# Placa_do_uControlador.net
KiCad netlist of a schematic drawn in Altium Designer
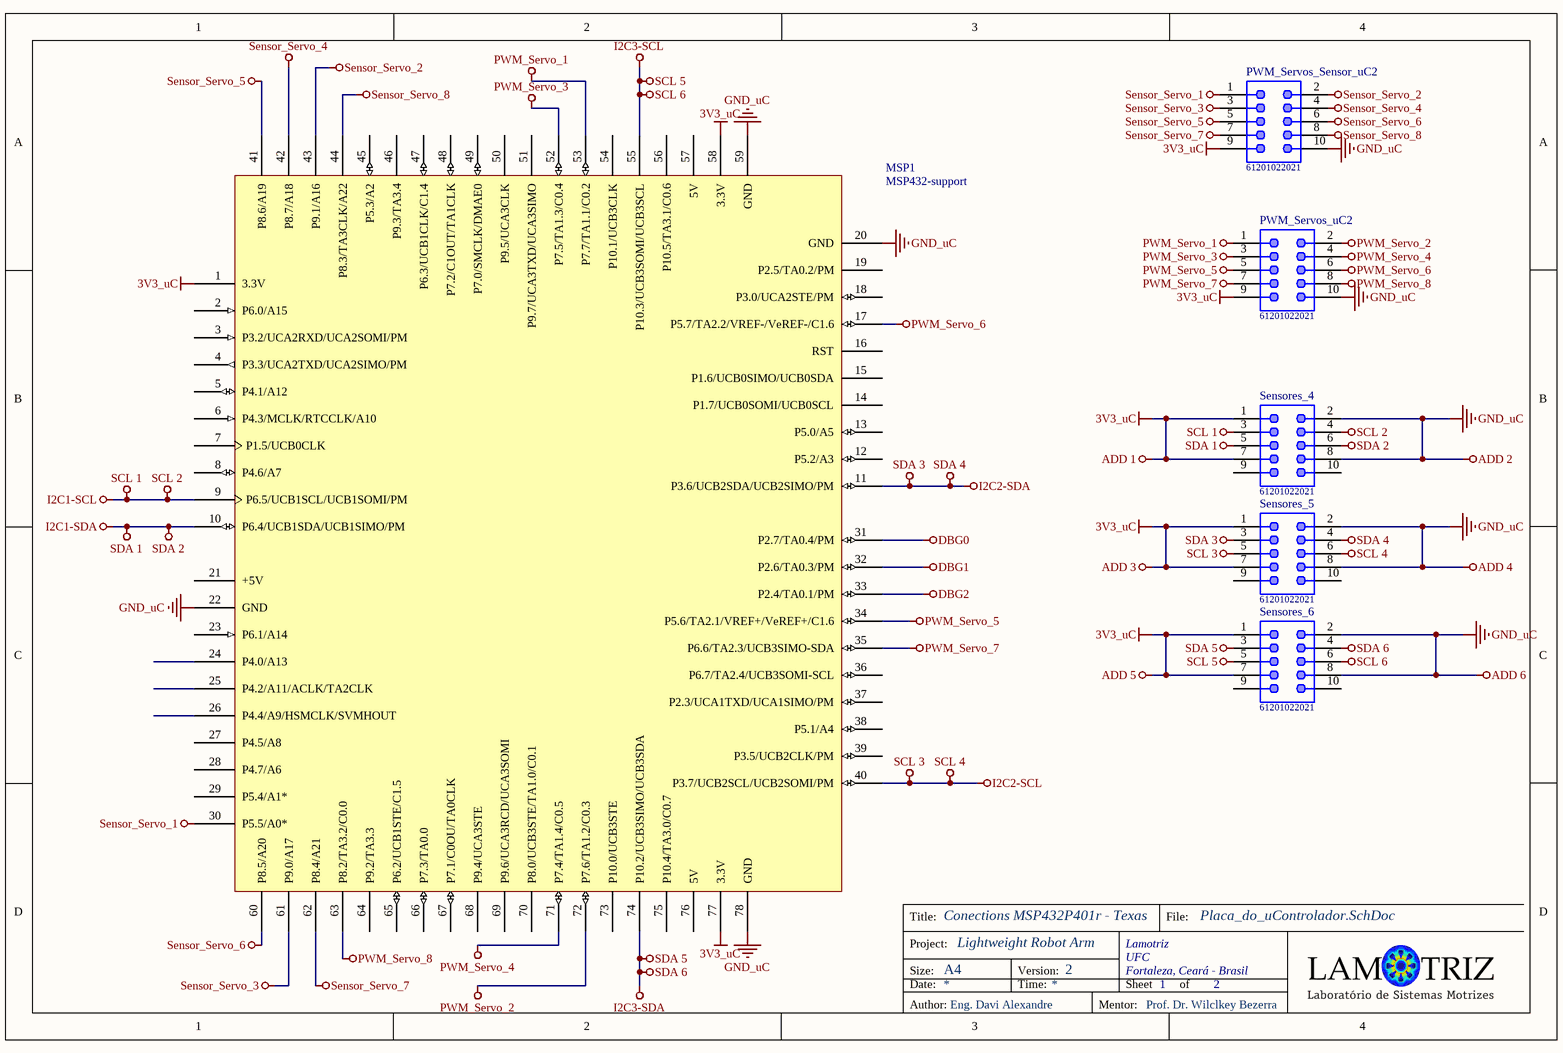
[diagram p0: Placa_do_uControlador.SchDoc]

(export (version "E")
  (design (tool "Eeschema 10.0.6"))
  (components
    (comp (ref "MSP1")
      (value "MSP432-support")
      (footprint "Msp432_Suport")
      (libsource (lib "Msp432_Suport") (part "U*"))
    )
    (comp (ref "PWM_Servos_Sensor_uC2")
      (value "61201022021")
      (footprint "61201022021")
      (description "Male Box Header WR-BHD with lever, THT, Vertical, pitch 2.54 mm, 10 pins")
      (fields (field (name "PUBLISHER") "Wurth Elektronik"))
      (libsource (lib "62504022021_Altium_WR-BHD_rev19a") (part "61201022021"))
    )
    (comp (ref "PWM_Servos_uC2")
      (value "61201022021")
      (footprint "61201022021")
      (description "Male Box Header WR-BHD with lever, THT, Vertical, pitch 2.54 mm, 10 pins")
      (fields (field (name "PUBLISHER") "Wurth Elektronik"))
      (libsource (lib "62504022021_Altium_WR-BHD_rev19a") (part "61201022021"))
    )
    (comp (ref "Sensores_4")
      (value "61201022021")
      (footprint "61201022021")
      (description "Male Box Header WR-BHD with lever, THT, Vertical, pitch 2.54 mm, 10 pins")
      (fields (field (name "PUBLISHER") "Wurth Elektronik"))
      (libsource (lib "62504022021_Altium_WR-BHD_rev19a") (part "61201022021"))
    )
    (comp (ref "Sensores_5")
      (value "61201022021")
      (footprint "61201022021")
      (description "Male Box Header WR-BHD with lever, THT, Vertical, pitch 2.54 mm, 10 pins")
      (fields (field (name "PUBLISHER") "Wurth Elektronik"))
      (libsource (lib "62504022021_Altium_WR-BHD_rev19a") (part "61201022021"))
    )
    (comp (ref "Sensores_6")
      (value "61201022021")
      (footprint "61201022021")
      (description "Male Box Header WR-BHD with lever, THT, Vertical, pitch 2.54 mm, 10 pins")
      (fields (field (name "PUBLISHER") "Wurth Elektronik"))
      (libsource (lib "62504022021_Altium_WR-BHD_rev19a") (part "61201022021"))
    )
  )
  (nets
    (net (code "1") (name "3V3_uC") (class "Default")
      (node (ref "MSP1") (pin "1") (pinfunction "3.3V_1") (pintype "power_in"))
      (node (ref "MSP1") (pin "58") (pinfunction "3.3V_58") (pintype "power_in"))
      (node (ref "MSP1") (pin "77") (pinfunction "3.3V_77") (pintype "power_in"))
      (node (ref "PWM_Servos_Sensor_uC2") (pin "9") (pinfunction "9_9") (pintype "passive"))
      (node (ref "PWM_Servos_uC2") (pin "9") (pinfunction "9_9") (pintype "passive"))
      (node (ref "Sensores_4") (pin "1") (pinfunction "1_1") (pintype "passive"))
      (node (ref "Sensores_4") (pin "7") (pinfunction "7_7") (pintype "passive"))
      (node (ref "Sensores_5") (pin "1") (pinfunction "1_1") (pintype "passive"))
      (node (ref "Sensores_5") (pin "7") (pinfunction "7_7") (pintype "passive"))
      (node (ref "Sensores_6") (pin "1") (pinfunction "1_1") (pintype "passive"))
      (node (ref "Sensores_6") (pin "7") (pinfunction "7_7") (pintype "passive"))
    )
    (net (code "2") (name "ADD 2") (class "Default")
      (node (ref "MSP1") (pin "20") (pinfunction "GND_20") (pintype "power_in"))
      (node (ref "MSP1") (pin "22") (pinfunction "GND_22") (pintype "passive"))
      (node (ref "MSP1") (pin "59") (pinfunction "GND_59") (pintype "power_in"))
      (node (ref "MSP1") (pin "78") (pinfunction "GND_78") (pintype "power_in"))
      (node (ref "PWM_Servos_Sensor_uC2") (pin "10") (pinfunction "10_10") (pintype "passive"))
      (node (ref "PWM_Servos_uC2") (pin "10") (pinfunction "10_10") (pintype "passive"))
      (node (ref "Sensores_4") (pin "2") (pinfunction "2_2") (pintype "passive"))
      (node (ref "Sensores_4") (pin "8") (pinfunction "8_8") (pintype "passive"))
      (node (ref "Sensores_5") (pin "2") (pinfunction "2_2") (pintype "passive"))
      (node (ref "Sensores_5") (pin "8") (pinfunction "8_8") (pintype "passive"))
      (node (ref "Sensores_6") (pin "2") (pinfunction "2_2") (pintype "passive"))
      (node (ref "Sensores_6") (pin "8") (pinfunction "8_8") (pintype "passive"))
    )
    (net (code "3") (name "DBG0") (class "Default")
      (node (ref "MSP1") (pin "31") (pinfunction "P2.7/TA0.4/PM_31") (pintype "bidirectional"))
    )
    (net (code "4") (name "DBG1") (class "Default")
      (node (ref "MSP1") (pin "32") (pinfunction "P2.6/TA0.3/PM_32") (pintype "bidirectional"))
    )
    (net (code "5") (name "DBG2") (class "Default")
      (node (ref "MSP1") (pin "33") (pinfunction "P2.4/TA0.1/PM_33") (pintype "bidirectional"))
    )
    (net (code "6") (name "I2C1-SCL") (class "Default")
      (node (ref "MSP1") (pin "9") (pinfunction "P6.5/UCB1SCL/UCB1SOMI/PM_9") (pintype "passive"))
      (node (ref "Sensores_4") (pin "3") (pinfunction "3_3") (pintype "passive"))
      (node (ref "Sensores_4") (pin "4") (pinfunction "4_4") (pintype "passive"))
    )
    (net (code "7") (name "I2C1-SDA") (class "Default")
      (node (ref "MSP1") (pin "10") (pinfunction "P6.4/UCB1SDA/UCB1SIMO/PM_10") (pintype "bidirectional"))
      (node (ref "Sensores_4") (pin "5") (pinfunction "5_5") (pintype "passive"))
      (node (ref "Sensores_4") (pin "6") (pinfunction "6_6") (pintype "passive"))
    )
    (net (code "8") (name "I2C2-SCL") (class "Default")
      (node (ref "MSP1") (pin "40") (pinfunction "P3.7/UCB2SCL/UCB2SOMI/PM_40") (pintype "bidirectional"))
      (node (ref "Sensores_5") (pin "5") (pinfunction "5_5") (pintype "passive"))
      (node (ref "Sensores_5") (pin "6") (pinfunction "6_6") (pintype "passive"))
    )
    (net (code "9") (name "I2C2-SDA") (class "Default")
      (node (ref "MSP1") (pin "11") (pinfunction "P3.6/UCB2SDA/UCB2SIMO/PM_11") (pintype "bidirectional"))
      (node (ref "Sensores_5") (pin "3") (pinfunction "3_3") (pintype "passive"))
      (node (ref "Sensores_5") (pin "4") (pinfunction "4_4") (pintype "passive"))
    )
    (net (code "10") (name "I2C3-SCL") (class "Default")
      (node (ref "MSP1") (pin "55") (pinfunction "P10.3/UCB3SOMI/UCB3SCL_55") (pintype "passive"))
      (node (ref "Sensores_6") (pin "5") (pinfunction "5_5") (pintype "passive"))
      (node (ref "Sensores_6") (pin "6") (pinfunction "6_6") (pintype "passive"))
    )
    (net (code "11") (name "I2C3-SDA") (class "Default")
      (node (ref "MSP1") (pin "74") (pinfunction "P10.2/UCB3SIMO/UCB3SDA_74") (pintype "passive"))
      (node (ref "Sensores_6") (pin "3") (pinfunction "3_3") (pintype "passive"))
      (node (ref "Sensores_6") (pin "4") (pinfunction "4_4") (pintype "passive"))
    )
    (net (code "12") (name "PWM_Servo_1") (class "Default")
      (node (ref "MSP1") (pin "53") (pinfunction "P7.7/TA1.1/C0.2_53") (pintype "bidirectional"))
      (node (ref "PWM_Servos_uC2") (pin "1") (pinfunction "1_1") (pintype "passive"))
    )
    (net (code "13") (name "PWM_Servo_2") (class "Default")
      (node (ref "MSP1") (pin "72") (pinfunction "P7.6/TA1.2/C0.3_72") (pintype "bidirectional"))
      (node (ref "PWM_Servos_uC2") (pin "2") (pinfunction "2_2") (pintype "passive"))
    )
    (net (code "14") (name "PWM_Servo_3") (class "Default")
      (node (ref "MSP1") (pin "52") (pinfunction "P7.5/TA1.3/C0.4_52") (pintype "bidirectional"))
      (node (ref "PWM_Servos_uC2") (pin "3") (pinfunction "3_3") (pintype "passive"))
    )
    (net (code "15") (name "PWM_Servo_4") (class "Default")
      (node (ref "MSP1") (pin "71") (pinfunction "P7.4/TA1.4/C0.5_71") (pintype "bidirectional"))
      (node (ref "PWM_Servos_uC2") (pin "4") (pinfunction "4_4") (pintype "passive"))
    )
    (net (code "16") (name "PWM_Servo_5") (class "Default")
      (node (ref "MSP1") (pin "34") (pinfunction "P5.6/TA2.1/VREF+/VeREF+/C1.6_34") (pintype "bidirectional"))
      (node (ref "PWM_Servos_uC2") (pin "5") (pinfunction "5_5") (pintype "passive"))
    )
    (net (code "17") (name "PWM_Servo_6") (class "Default")
      (node (ref "MSP1") (pin "17") (pinfunction "P5.7/TA2.2/VREF-/VeREF-/C1.6_17") (pintype "bidirectional"))
      (node (ref "PWM_Servos_uC2") (pin "6") (pinfunction "6_6") (pintype "passive"))
    )
    (net (code "18") (name "PWM_Servo_7") (class "Default")
      (node (ref "MSP1") (pin "35") (pinfunction "P6.6/TA2.3/UCB3SIMO-SDA_35") (pintype "bidirectional"))
      (node (ref "PWM_Servos_uC2") (pin "7") (pinfunction "7_7") (pintype "passive"))
    )
    (net (code "19") (name "PWM_Servo_8") (class "Default")
      (node (ref "MSP1") (pin "63") (pinfunction "P8.2/TA3.2/C0.0_63") (pintype "passive"))
      (node (ref "PWM_Servos_uC2") (pin "8") (pinfunction "8_8") (pintype "passive"))
    )
    (net (code "20") (name "Sensor_Servo_1") (class "Default")
      (node (ref "MSP1") (pin "30") (pinfunction "P5.5/A0*_30") (pintype "passive"))
      (node (ref "PWM_Servos_Sensor_uC2") (pin "1") (pinfunction "1_1") (pintype "passive"))
    )
    (net (code "21") (name "Sensor_Servo_2") (class "Default")
      (node (ref "MSP1") (pin "43") (pinfunction "P9.1/A16_43") (pintype "passive"))
      (node (ref "PWM_Servos_Sensor_uC2") (pin "2") (pinfunction "2_2") (pintype "passive"))
    )
    (net (code "22") (name "Sensor_Servo_3") (class "Default")
      (node (ref "MSP1") (pin "61") (pinfunction "P9.0/A17_61") (pintype "passive"))
      (node (ref "PWM_Servos_Sensor_uC2") (pin "3") (pinfunction "3_3") (pintype "passive"))
    )
    (net (code "23") (name "Sensor_Servo_4") (class "Default")
      (node (ref "MSP1") (pin "42") (pinfunction "P8.7/A18_42") (pintype "passive"))
      (node (ref "PWM_Servos_Sensor_uC2") (pin "4") (pinfunction "4_4") (pintype "passive"))
    )
    (net (code "24") (name "Sensor_Servo_5") (class "Default")
      (node (ref "MSP1") (pin "41") (pinfunction "P8.6/A19_41") (pintype "passive"))
      (node (ref "PWM_Servos_Sensor_uC2") (pin "5") (pinfunction "5_5") (pintype "passive"))
    )
    (net (code "25") (name "Sensor_Servo_6") (class "Default")
      (node (ref "MSP1") (pin "60") (pinfunction "P8.5/A20_60") (pintype "passive"))
      (node (ref "PWM_Servos_Sensor_uC2") (pin "6") (pinfunction "6_6") (pintype "passive"))
    )
    (net (code "26") (name "Sensor_Servo_7") (class "Default")
      (node (ref "MSP1") (pin "62") (pinfunction "P8.4/A21_62") (pintype "passive"))
      (node (ref "PWM_Servos_Sensor_uC2") (pin "7") (pinfunction "7_7") (pintype "passive"))
    )
    (net (code "27") (name "Sensor_Servo_8") (class "Default")
      (node (ref "MSP1") (pin "44") (pinfunction "P8.3/TA3CLK/A22_44") (pintype "passive"))
      (node (ref "PWM_Servos_Sensor_uC2") (pin "8") (pinfunction "8_8") (pintype "passive"))
    )
    (net (code "28") (name "unconnected-(MSP1-+5V-Pad21)") (class "Default")
      (node (ref "MSP1") (pin "21") (pinfunction "+5V_21") (pintype "power_in"))
    )
    (net (code "29") (name "unconnected-(MSP1-5V-Pad57)") (class "Default")
      (node (ref "MSP1") (pin "57") (pinfunction "5V_57") (pintype "power_in"))
    )
    (net (code "30") (name "unconnected-(MSP1-5V-Pad76)") (class "Default")
      (node (ref "MSP1") (pin "76") (pinfunction "5V_76") (pintype "power_in"))
    )
    (net (code "31") (name "unconnected-(MSP1-P1.5{slash}UCB0CLK-Pad7)") (class "Default")
      (node (ref "MSP1") (pin "7") (pinfunction "P1.5/UCB0CLK_7") (pintype "passive"))
    )
    (net (code "32") (name "unconnected-(MSP1-P1.6{slash}UCB0SIMO{slash}UCB0SDA-Pad15)") (class "Default")
      (node (ref "MSP1") (pin "15") (pinfunction "P1.6/UCB0SIMO/UCB0SDA_15") (pintype "passive"))
    )
    (net (code "33") (name "unconnected-(MSP1-P1.7{slash}UCB0SOMI{slash}UCB0SCL-Pad14)") (class "Default")
      (node (ref "MSP1") (pin "14") (pinfunction "P1.7/UCB0SOMI/UCB0SCL_14") (pintype "passive"))
    )
    (net (code "34") (name "unconnected-(MSP1-P2.3{slash}UCA1TXD{slash}UCA1SIMO{slash}PM-Pad37)") (class "Default")
      (node (ref "MSP1") (pin "37") (pinfunction "P2.3/UCA1TXD/UCA1SIMO/PM_37") (pintype "bidirectional"))
    )
    (net (code "35") (name "unconnected-(MSP1-P2.5{slash}TA0.2{slash}PM-Pad19)") (class "Default")
      (node (ref "MSP1") (pin "19") (pinfunction "P2.5/TA0.2/PM_19") (pintype "passive"))
    )
    (net (code "36") (name "unconnected-(MSP1-P3.0{slash}UCA2STE{slash}PM-Pad18)") (class "Default")
      (node (ref "MSP1") (pin "18") (pinfunction "P3.0/UCA2STE/PM_18") (pintype "bidirectional"))
    )
    (net (code "37") (name "unconnected-(MSP1-P3.2{slash}UCA2RXD{slash}UCA2SOMI{slash}PM-Pad3)") (class "Default")
      (node (ref "MSP1") (pin "3") (pinfunction "P3.2/UCA2RXD/UCA2SOMI/PM_3") (pintype "input"))
    )
    (net (code "38") (name "unconnected-(MSP1-P3.3{slash}UCA2TXD{slash}UCA2SIMO{slash}PM-Pad4)") (class "Default")
      (node (ref "MSP1") (pin "4") (pinfunction "P3.3/UCA2TXD/UCA2SIMO/PM_4") (pintype "output"))
    )
    (net (code "39") (name "unconnected-(MSP1-P3.5{slash}UCB2CLK{slash}PM-Pad39)") (class "Default")
      (node (ref "MSP1") (pin "39") (pinfunction "P3.5/UCB2CLK/PM_39") (pintype "bidirectional"))
    )
    (net (code "40") (name "unconnected-(MSP1-P4.0{slash}A13-Pad24)") (class "Default")
      (node (ref "MSP1") (pin "24") (pinfunction "P4.0/A13_24") (pintype "passive"))
    )
    (net (code "41") (name "unconnected-(MSP1-P4.1{slash}A12-Pad5)") (class "Default")
      (node (ref "MSP1") (pin "5") (pinfunction "P4.1/A12_5") (pintype "bidirectional"))
    )
    (net (code "42") (name "unconnected-(MSP1-P4.2{slash}A11{slash}ACLK{slash}TA2CLK-Pad25)") (class "Default")
      (node (ref "MSP1") (pin "25") (pinfunction "P4.2/A11/ACLK/TA2CLK_25") (pintype "passive"))
    )
    (net (code "43") (name "unconnected-(MSP1-P4.3{slash}MCLK{slash}RTCCLK{slash}A10-Pad6)") (class "Default")
      (node (ref "MSP1") (pin "6") (pinfunction "P4.3/MCLK/RTCCLK/A10_6") (pintype "input"))
    )
    (net (code "44") (name "unconnected-(MSP1-P4.4{slash}A9{slash}HSMCLK{slash}SVMHOUT-Pad26)") (class "Default")
      (node (ref "MSP1") (pin "26") (pinfunction "P4.4/A9/HSMCLK/SVMHOUT_26") (pintype "passive"))
    )
    (net (code "45") (name "unconnected-(MSP1-P4.5{slash}A8-Pad27)") (class "Default")
      (node (ref "MSP1") (pin "27") (pinfunction "P4.5/A8_27") (pintype "passive"))
    )
    (net (code "46") (name "unconnected-(MSP1-P4.6{slash}A7-Pad8)") (class "Default")
      (node (ref "MSP1") (pin "8") (pinfunction "P4.6/A7_8") (pintype "bidirectional"))
    )
    (net (code "47") (name "unconnected-(MSP1-P4.7{slash}A6-Pad28)") (class "Default")
      (node (ref "MSP1") (pin "28") (pinfunction "P4.7/A6_28") (pintype "passive"))
    )
    (net (code "48") (name "unconnected-(MSP1-P5.0{slash}A5-Pad13)") (class "Default")
      (node (ref "MSP1") (pin "13") (pinfunction "P5.0/A5_13") (pintype "bidirectional"))
    )
    (net (code "49") (name "unconnected-(MSP1-P5.1{slash}A4-Pad38)") (class "Default")
      (node (ref "MSP1") (pin "38") (pinfunction "P5.1/A4_38") (pintype "bidirectional"))
    )
    (net (code "50") (name "unconnected-(MSP1-P5.2{slash}A3-Pad12)") (class "Default")
      (node (ref "MSP1") (pin "12") (pinfunction "P5.2/A3_12") (pintype "bidirectional"))
    )
    (net (code "51") (name "unconnected-(MSP1-P5.3{slash}A2-Pad45)") (class "Default")
      (node (ref "MSP1") (pin "45") (pinfunction "P5.3/A2_45") (pintype "bidirectional"))
    )
    (net (code "52") (name "unconnected-(MSP1-P5.4{slash}A1*-Pad29)") (class "Default")
      (node (ref "MSP1") (pin "29") (pinfunction "P5.4/A1*_29") (pintype "passive"))
    )
    (net (code "53") (name "unconnected-(MSP1-P6.0{slash}A15-Pad2)") (class "Default")
      (node (ref "MSP1") (pin "2") (pinfunction "P6.0/A15_2") (pintype "input"))
    )
    (net (code "54") (name "unconnected-(MSP1-P6.1{slash}A14-Pad23)") (class "Default")
      (node (ref "MSP1") (pin "23") (pinfunction "P6.1/A14_23") (pintype "input"))
    )
    (net (code "55") (name "unconnected-(MSP1-P6.2{slash}UCB1STE{slash}C1.5-Pad65)") (class "Default")
      (node (ref "MSP1") (pin "65") (pinfunction "P6.2/UCB1STE/C1.5_65") (pintype "bidirectional"))
    )
    (net (code "56") (name "unconnected-(MSP1-P6.3{slash}UCB1CLK{slash}C1.4-Pad47)") (class "Default")
      (node (ref "MSP1") (pin "47") (pinfunction "P6.3/UCB1CLK/C1.4_47") (pintype "bidirectional"))
    )
    (net (code "57") (name "unconnected-(MSP1-P6.7{slash}TA2.4{slash}UCB3SOMI-SCL-Pad36)") (class "Default")
      (node (ref "MSP1") (pin "36") (pinfunction "P6.7/TA2.4/UCB3SOMI-SCL_36") (pintype "bidirectional"))
    )
    (net (code "58") (name "unconnected-(MSP1-P7.0{slash}SMCLK{slash}DMAE0-Pad49)") (class "Default")
      (node (ref "MSP1") (pin "49") (pinfunction "P7.0/SMCLK/DMAE0_49") (pintype "bidirectional"))
    )
    (net (code "59") (name "unconnected-(MSP1-P7.1{slash}C0OU{slash}TA0CLK-Pad67)") (class "Default")
      (node (ref "MSP1") (pin "67") (pinfunction "P7.1/C0OU/TA0CLK_67") (pintype "bidirectional"))
    )
    (net (code "60") (name "unconnected-(MSP1-P7.2{slash}C1OUT{slash}TA1CLK-Pad48)") (class "Default")
      (node (ref "MSP1") (pin "48") (pinfunction "P7.2/C1OUT/TA1CLK_48") (pintype "bidirectional"))
    )
    (net (code "61") (name "unconnected-(MSP1-P7.3{slash}TA0.0-Pad66)") (class "Default")
      (node (ref "MSP1") (pin "66") (pinfunction "P7.3/TA0.0_66") (pintype "bidirectional"))
    )
    (net (code "62") (name "unconnected-(MSP1-P8.0{slash}UCB3STE{slash}TA1.0{slash}C0.1-Pad70)") (class "Default")
      (node (ref "MSP1") (pin "70") (pinfunction "P8.0/UCB3STE/TA1.0/C0.1_70") (pintype "passive"))
    )
    (net (code "63") (name "unconnected-(MSP1-P9.2{slash}TA3.3-Pad64)") (class "Default")
      (node (ref "MSP1") (pin "64") (pinfunction "P9.2/TA3.3_64") (pintype "passive"))
    )
    (net (code "64") (name "unconnected-(MSP1-P9.3{slash}TA3.4-Pad46)") (class "Default")
      (node (ref "MSP1") (pin "46") (pinfunction "P9.3/TA3.4_46") (pintype "passive"))
    )
    (net (code "65") (name "unconnected-(MSP1-P9.4{slash}UCA3STE-Pad68)") (class "Default")
      (node (ref "MSP1") (pin "68") (pinfunction "P9.4/UCA3STE_68") (pintype "passive"))
    )
    (net (code "66") (name "unconnected-(MSP1-P9.5{slash}UCA3CLK-Pad50)") (class "Default")
      (node (ref "MSP1") (pin "50") (pinfunction "P9.5/UCA3CLK_50") (pintype "passive"))
    )
    (net (code "67") (name "unconnected-(MSP1-P9.6{slash}UCA3RCD{slash}UCA3SOMI-Pad69)") (class "Default")
      (node (ref "MSP1") (pin "69") (pinfunction "P9.6/UCA3RCD/UCA3SOMI_69") (pintype "passive"))
    )
    (net (code "68") (name "unconnected-(MSP1-P9.7{slash}UCA3TXD{slash}UCA3SIMO-Pad51)") (class "Default")
      (node (ref "MSP1") (pin "51") (pinfunction "P9.7/UCA3TXD/UCA3SIMO_51") (pintype "passive"))
    )
    (net (code "69") (name "unconnected-(MSP1-P10.0{slash}UCB3STE-Pad73)") (class "Default")
      (node (ref "MSP1") (pin "73") (pinfunction "P10.0/UCB3STE_73") (pintype "passive"))
    )
    (net (code "70") (name "unconnected-(MSP1-P10.1{slash}UCB3CLK-Pad54)") (class "Default")
      (node (ref "MSP1") (pin "54") (pinfunction "P10.1/UCB3CLK_54") (pintype "passive"))
    )
    (net (code "71") (name "unconnected-(MSP1-P10.4{slash}TA3.0{slash}C0.7-Pad75)") (class "Default")
      (node (ref "MSP1") (pin "75") (pinfunction "P10.4/TA3.0/C0.7_75") (pintype "passive"))
    )
    (net (code "72") (name "unconnected-(MSP1-P10.5{slash}TA3.1{slash}C0.6-Pad56)") (class "Default")
      (node (ref "MSP1") (pin "56") (pinfunction "P10.5/TA3.1/C0.6_56") (pintype "passive"))
    )
    (net (code "73") (name "unconnected-(MSP1-RST-Pad16)") (class "Default")
      (node (ref "MSP1") (pin "16") (pinfunction "RST_16") (pintype "passive"))
    )
    (net (code "74") (name "unconnected-(Sensores_4-Pad9)") (class "Default")
      (node (ref "Sensores_4") (pin "9") (pinfunction "9_9") (pintype "passive"))
    )
    (net (code "75") (name "unconnected-(Sensores_4-Pad10)") (class "Default")
      (node (ref "Sensores_4") (pin "10") (pinfunction "10_10") (pintype "passive"))
    )
    (net (code "76") (name "unconnected-(Sensores_5-Pad9)") (class "Default")
      (node (ref "Sensores_5") (pin "9") (pinfunction "9_9") (pintype "passive"))
    )
    (net (code "77") (name "unconnected-(Sensores_5-Pad10)") (class "Default")
      (node (ref "Sensores_5") (pin "10") (pinfunction "10_10") (pintype "passive"))
    )
    (net (code "78") (name "unconnected-(Sensores_6-Pad9)") (class "Default")
      (node (ref "Sensores_6") (pin "9") (pinfunction "9_9") (pintype "passive"))
    )
    (net (code "79") (name "unconnected-(Sensores_6-Pad10)") (class "Default")
      (node (ref "Sensores_6") (pin "10") (pinfunction "10_10") (pintype "passive"))
    )
  )
)
